# TMC5160_SPI_rev2.net
KiCad netlist of a schematic drawn in EAGLE
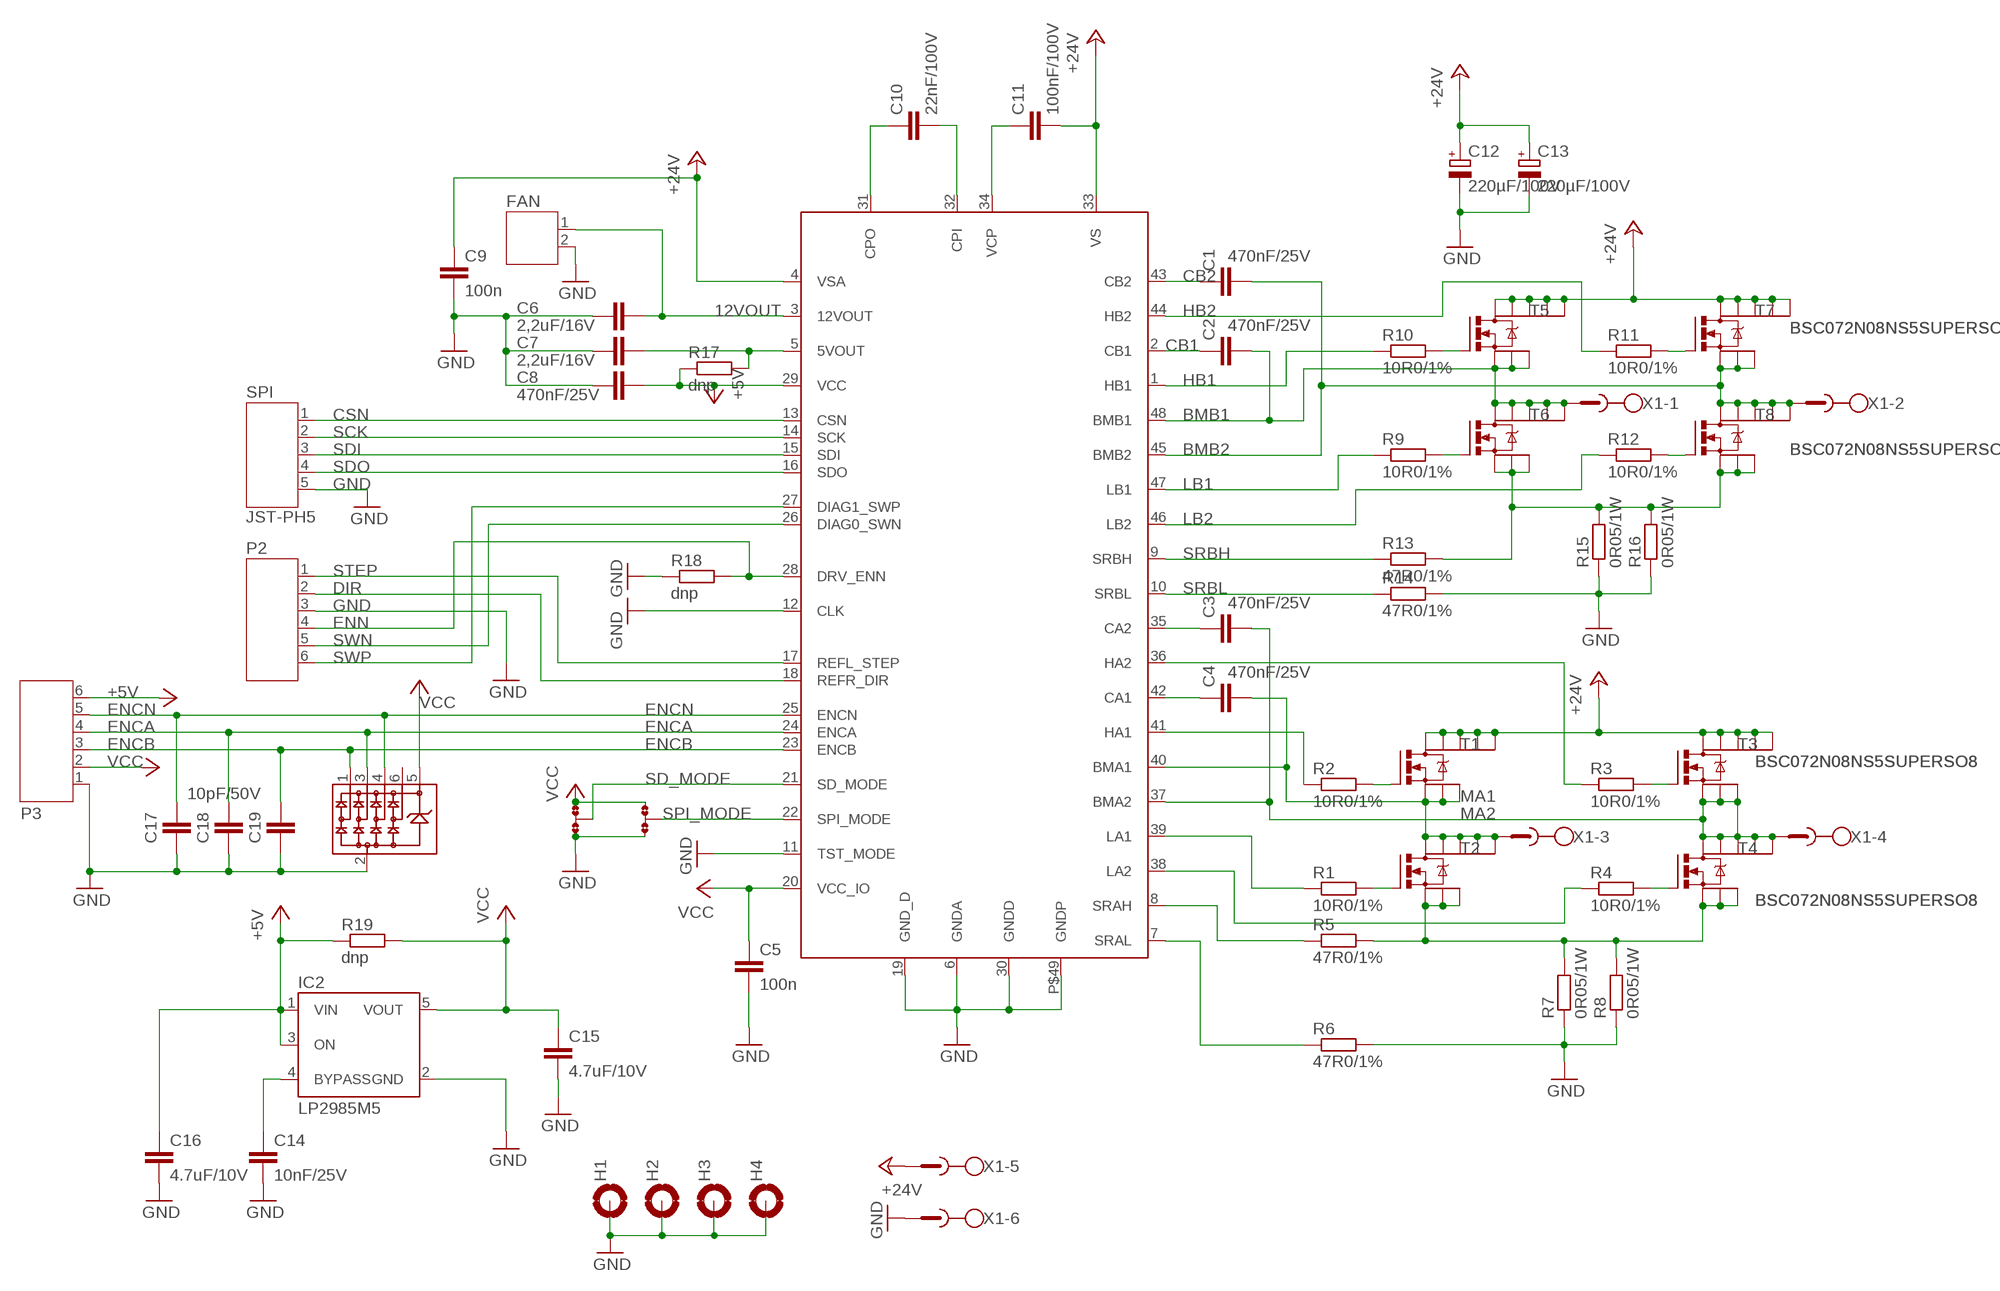
[diagram p0: schematic, sheet 1]

(export (version "E")
  (design (tool "Eeschema 10.0.6"))
  (components
    (comp (ref "C1")
      (value "470nF/25V")
      (footprint "eagle-import:C0805")
      (libsource (lib "eagle-import") (part "C-EUC0805"))
    )
    (comp (ref "C2")
      (value "470nF/25V")
      (footprint "eagle-import:C0805")
      (libsource (lib "eagle-import") (part "C-EUC0805"))
    )
    (comp (ref "C3")
      (value "470nF/25V")
      (footprint "eagle-import:C0805")
      (libsource (lib "eagle-import") (part "C-EUC0805"))
    )
    (comp (ref "C4")
      (value "470nF/25V")
      (footprint "eagle-import:C0805")
      (libsource (lib "eagle-import") (part "C-EUC0805"))
    )
    (comp (ref "C5")
      (value "100n")
      (footprint "eagle-import:C0603")
      (libsource (lib "eagle-import") (part "C-EUC0603"))
    )
    (comp (ref "C6")
      (value "2,2uF/16V")
      (footprint "eagle-import:C0805")
      (libsource (lib "eagle-import") (part "C-EUC0805"))
    )
    (comp (ref "C7")
      (value "2,2uF/16V")
      (footprint "eagle-import:C0805")
      (libsource (lib "eagle-import") (part "C-EUC0805"))
    )
    (comp (ref "C8")
      (value "470nF/25V")
      (footprint "eagle-import:C0805")
      (libsource (lib "eagle-import") (part "C-EUC0805"))
    )
    (comp (ref "C9")
      (value "100n")
      (footprint "eagle-import:C0603")
      (libsource (lib "eagle-import") (part "C-EUC0603"))
    )
    (comp (ref "C10")
      (value "22nF/100V")
      (footprint "eagle-import:C0805")
      (libsource (lib "eagle-import") (part "C-EUC0805"))
    )
    (comp (ref "C11")
      (value "100nF/100V")
      (footprint "eagle-import:C0805")
      (libsource (lib "eagle-import") (part "C-EUC0805"))
    )
    (comp (ref "C12")
      (value "220µF/100V")
      (footprint "eagle-import:153CLV-1014")
      (libsource (lib "eagle-import") (part "CPOL-EU153CLV-1014"))
    )
    (comp (ref "C13")
      (value "220µF/100V")
      (footprint "eagle-import:153CLV-1014")
      (libsource (lib "eagle-import") (part "CPOL-EU153CLV-1014"))
    )
    (comp (ref "C14")
      (value "10nF/25V")
      (footprint "eagle-import:C0603")
      (libsource (lib "eagle-import") (part "C-EUC0603"))
    )
    (comp (ref "C15")
      (value "4.7uF/10V")
      (footprint "eagle-import:C0603")
      (libsource (lib "eagle-import") (part "C-EUC0603"))
    )
    (comp (ref "C16")
      (value "4.7uF/10V")
      (footprint "eagle-import:C0603")
      (libsource (lib "eagle-import") (part "C-EUC0603"))
    )
    (comp (ref "C17")
      (value "10pF/50V")
      (footprint "eagle-import:C0603")
      (libsource (lib "eagle-import") (part "C-EUC0603"))
    )
    (comp (ref "C18")
      (value "10pF/50V")
      (footprint "eagle-import:C0603")
      (libsource (lib "eagle-import") (part "C-EUC0603"))
    )
    (comp (ref "C19")
      (value "10pF/50V")
      (footprint "eagle-import:C0603")
      (libsource (lib "eagle-import") (part "C-EUC0603"))
    )
    (comp (ref "D1")
      (value "SRV05-4SOT23-6-3D")
      (footprint "eagle-import:SOT23-6")
      (libsource (lib "eagle-import") (part "SRV05-4SOT23-6-3D"))
    )
    (comp (ref "FAN")
      (value "JST-PH2")
      (footprint "eagle-import:JST-PH2")
      (libsource (lib "eagle-import") (part "JST-PH2"))
    )
    (comp (ref "H1")
      (value "MOUNT-PAD-ROUND3.2")
      (footprint "eagle-import:3,2-PAD")
      (libsource (lib "eagle-import") (part "MOUNT-PAD-ROUND3.2"))
    )
    (comp (ref "H2")
      (value "MOUNT-PAD-ROUND3.2")
      (footprint "eagle-import:3,2-PAD")
      (libsource (lib "eagle-import") (part "MOUNT-PAD-ROUND3.2"))
    )
    (comp (ref "H3")
      (value "MOUNT-PAD-ROUND3.2")
      (footprint "eagle-import:3,2-PAD")
      (libsource (lib "eagle-import") (part "MOUNT-PAD-ROUND3.2"))
    )
    (comp (ref "H4")
      (value "MOUNT-PAD-ROUND3.2")
      (footprint "eagle-import:3,2-PAD")
      (libsource (lib "eagle-import") (part "MOUNT-PAD-ROUND3.2"))
    )
    (comp (ref "IC2")
      (value "LP2985M5")
      (footprint "eagle-import:SOT23-5")
      (libsource (lib "eagle-import") (part "LP2985M5"))
    )
    (comp (ref "JMP1")
      (value "0R-JUMPA")
      (footprint "eagle-import:A0R-JMP")
      (libsource (lib "eagle-import") (part "0R-JUMPA"))
    )
    (comp (ref "JMP2")
      (value "0R-JUMPA")
      (footprint "eagle-import:A0R-JMP")
      (libsource (lib "eagle-import") (part "0R-JUMPA"))
    )
    (comp (ref "P2")
      (value "JST-PH6")
      (footprint "eagle-import:JST-PH6")
      (libsource (lib "eagle-import") (part "JST-PH6"))
    )
    (comp (ref "P3")
      (value "JST-PH6")
      (footprint "eagle-import:JST-PH6")
      (libsource (lib "eagle-import") (part "JST-PH6"))
    )
    (comp (ref "R1")
      (value "10R0/1%")
      (footprint "eagle-import:R0603")
      (libsource (lib "eagle-import") (part "R-EU_R0603"))
    )
    (comp (ref "R2")
      (value "10R0/1%")
      (footprint "eagle-import:R0603")
      (libsource (lib "eagle-import") (part "R-EU_R0603"))
    )
    (comp (ref "R3")
      (value "10R0/1%")
      (footprint "eagle-import:R0603")
      (libsource (lib "eagle-import") (part "R-EU_R0603"))
    )
    (comp (ref "R4")
      (value "10R0/1%")
      (footprint "eagle-import:R0603")
      (libsource (lib "eagle-import") (part "R-EU_R0603"))
    )
    (comp (ref "R5")
      (value "47R0/1%")
      (footprint "eagle-import:R0603")
      (libsource (lib "eagle-import") (part "R-EU_R0603"))
    )
    (comp (ref "R6")
      (value "47R0/1%")
      (footprint "eagle-import:R0603")
      (libsource (lib "eagle-import") (part "R-EU_R0603"))
    )
    (comp (ref "R7")
      (value "0R05/1W")
      (footprint "eagle-import:R3225")
      (libsource (lib "eagle-import") (part "R-EU_R3225"))
    )
    (comp (ref "R8")
      (value "0R05/1W")
      (footprint "eagle-import:R3225")
      (libsource (lib "eagle-import") (part "R-EU_R3225"))
    )
    (comp (ref "R9")
      (value "10R0/1%")
      (footprint "eagle-import:R0603")
      (libsource (lib "eagle-import") (part "R-EU_R0603"))
    )
    (comp (ref "R10")
      (value "10R0/1%")
      (footprint "eagle-import:R0603")
      (libsource (lib "eagle-import") (part "R-EU_R0603"))
    )
    (comp (ref "R11")
      (value "10R0/1%")
      (footprint "eagle-import:R0603")
      (libsource (lib "eagle-import") (part "R-EU_R0603"))
    )
    (comp (ref "R12")
      (value "10R0/1%")
      (footprint "eagle-import:R0603")
      (libsource (lib "eagle-import") (part "R-EU_R0603"))
    )
    (comp (ref "R13")
      (value "47R0/1%")
      (footprint "eagle-import:R0603")
      (libsource (lib "eagle-import") (part "R-EU_R0603"))
    )
    (comp (ref "R14")
      (value "47R0/1%")
      (footprint "eagle-import:R0603")
      (libsource (lib "eagle-import") (part "R-EU_R0603"))
    )
    (comp (ref "R15")
      (value "0R05/1W")
      (footprint "eagle-import:R3225")
      (libsource (lib "eagle-import") (part "R-EU_R3225"))
    )
    (comp (ref "R16")
      (value "0R05/1W")
      (footprint "eagle-import:R3225")
      (libsource (lib "eagle-import") (part "R-EU_R3225"))
    )
    (comp (ref "R17")
      (value "dnp")
      (footprint "eagle-import:R0603")
      (libsource (lib "eagle-import") (part "R-EU_R0603"))
    )
    (comp (ref "R18")
      (value "dnp")
      (footprint "eagle-import:R0603")
      (libsource (lib "eagle-import") (part "R-EU_R0603"))
    )
    (comp (ref "R19")
      (value "dnp")
      (footprint "eagle-import:R0603")
      (libsource (lib "eagle-import") (part "R-EU_R0603"))
    )
    (comp (ref "SPI")
      (value "JST-PH5")
      (footprint "eagle-import:JST-PH5")
      (libsource (lib "eagle-import") (part "JST-PH5"))
    )
    (comp (ref "T1")
      (value "BSC072N08NS5SUPERSO8")
      (footprint "eagle-import:SOTFL127P615X110-8")
      (libsource (lib "eagle-import") (part "BSC072N08NS5SUPERSO8"))
    )
    (comp (ref "T2")
      (value "BSC072N08NS5SUPERSO8")
      (footprint "eagle-import:SOTFL127P615X110-8")
      (libsource (lib "eagle-import") (part "BSC072N08NS5SUPERSO8"))
    )
    (comp (ref "T3")
      (value "BSC072N08NS5SUPERSO8")
      (footprint "eagle-import:SOTFL127P615X110-8")
      (libsource (lib "eagle-import") (part "BSC072N08NS5SUPERSO8"))
    )
    (comp (ref "T4")
      (value "BSC072N08NS5SUPERSO8")
      (footprint "eagle-import:SOTFL127P615X110-8")
      (libsource (lib "eagle-import") (part "BSC072N08NS5SUPERSO8"))
    )
    (comp (ref "T5")
      (value "BSC072N08NS5SUPERSO8")
      (footprint "eagle-import:SOTFL127P615X110-8")
      (libsource (lib "eagle-import") (part "BSC072N08NS5SUPERSO8"))
    )
    (comp (ref "T6")
      (value "BSC072N08NS5SUPERSO8")
      (footprint "eagle-import:SOTFL127P615X110-8")
      (libsource (lib "eagle-import") (part "BSC072N08NS5SUPERSO8"))
    )
    (comp (ref "T7")
      (value "BSC072N08NS5SUPERSO8")
      (footprint "eagle-import:SOTFL127P615X110-8")
      (libsource (lib "eagle-import") (part "BSC072N08NS5SUPERSO8"))
    )
    (comp (ref "T8")
      (value "BSC072N08NS5SUPERSO8")
      (footprint "eagle-import:SOTFL127P615X110-8")
      (libsource (lib "eagle-import") (part "BSC072N08NS5SUPERSO8"))
    )
    (comp (ref "TMC5160")
      (value "TMC5160-TA")
      (footprint "eagle-import:QFP50P900X900X120-48")
      (libsource (lib "eagle-import") (part "TMC5160-TA"))
    )
    (comp (ref "X1")
      (value "AKL166-06")
      (footprint "eagle-import:AKL166-06")
      (libsource (lib "eagle-import") (part "AKL166-06"))
    )
  )
  (nets
    (net (code "1") (name "+5V") (class "Default")
      (node (ref "C16") (pin "1") (pinfunction "1_1") (pintype "passive"))
      (node (ref "C8") (pin "2") (pinfunction "2_2") (pintype "passive"))
      (node (ref "IC2") (pin "1") (pinfunction "VIN_1") (pintype "power_in"))
      (node (ref "IC2") (pin "3") (pinfunction "ON_3") (pintype "input"))
      (node (ref "P3") (pin "6") (pinfunction "6_6") (pintype "passive"))
      (node (ref "R17") (pin "1") (pinfunction "1_1") (pintype "passive"))
      (node (ref "R19") (pin "1") (pinfunction "1_1") (pintype "passive"))
      (node (ref "TMC5160") (pin "29") (pinfunction "VCC_29") (pintype "bidirectional"))
    )
    (net (code "2") (name "+24V") (class "Default")
      (node (ref "C11") (pin "2") (pinfunction "2_2") (pintype "passive"))
      (node (ref "C12") (pin "+") (pinfunction "+_+") (pintype "passive"))
      (node (ref "C13") (pin "+") (pinfunction "+_+") (pintype "passive"))
      (node (ref "C9") (pin "1") (pinfunction "1_1") (pintype "passive"))
      (node (ref "T1") (pin "D") (pinfunction "D_D") (pintype "passive"))
      (node (ref "T1") (pin "D5") (pinfunction "D1_D5") (pintype "passive"))
      (node (ref "T1") (pin "D6") (pinfunction "D2_D6") (pintype "passive"))
      (node (ref "T1") (pin "D7") (pinfunction "D3_D7") (pintype "passive"))
      (node (ref "T1") (pin "D8") (pinfunction "D4_D8") (pintype "passive"))
      (node (ref "T3") (pin "D") (pinfunction "D_D") (pintype "passive"))
      (node (ref "T3") (pin "D5") (pinfunction "D1_D5") (pintype "passive"))
      (node (ref "T3") (pin "D6") (pinfunction "D2_D6") (pintype "passive"))
      (node (ref "T3") (pin "D7") (pinfunction "D3_D7") (pintype "passive"))
      (node (ref "T3") (pin "D8") (pinfunction "D4_D8") (pintype "passive"))
      (node (ref "T5") (pin "D") (pinfunction "D_D") (pintype "passive"))
      (node (ref "T5") (pin "D5") (pinfunction "D1_D5") (pintype "passive"))
      (node (ref "T5") (pin "D6") (pinfunction "D2_D6") (pintype "passive"))
      (node (ref "T5") (pin "D7") (pinfunction "D3_D7") (pintype "passive"))
      (node (ref "T5") (pin "D8") (pinfunction "D4_D8") (pintype "passive"))
      (node (ref "T7") (pin "D") (pinfunction "D_D") (pintype "passive"))
      (node (ref "T7") (pin "D5") (pinfunction "D1_D5") (pintype "passive"))
      (node (ref "T7") (pin "D6") (pinfunction "D2_D6") (pintype "passive"))
      (node (ref "T7") (pin "D7") (pinfunction "D3_D7") (pintype "passive"))
      (node (ref "T7") (pin "D8") (pinfunction "D4_D8") (pintype "passive"))
      (node (ref "TMC5160") (pin "33") (pinfunction "VS_33") (pintype "bidirectional"))
      (node (ref "TMC5160") (pin "4") (pinfunction "VSA_4") (pintype "bidirectional"))
      (node (ref "X1") (pin "5") (pinfunction "SK_5") (pintype "passive"))
    )
    (net (code "3") (name "/12VOUT") (class "Default")
      (node (ref "C6") (pin "2") (pinfunction "2_2") (pintype "passive"))
      (node (ref "FAN") (pin "1") (pinfunction "1_1") (pintype "passive"))
      (node (ref "TMC5160") (pin "3") (pinfunction "12VOUT_3") (pintype "bidirectional"))
    )
    (net (code "4") (name "/BMB1") (class "Default")
      (node (ref "C2") (pin "2") (pinfunction "2_2") (pintype "passive"))
      (node (ref "T5") (pin "S1") (pinfunction "S1_S1") (pintype "passive"))
      (node (ref "T5") (pin "S2") (pinfunction "S2_S2") (pintype "passive"))
      (node (ref "T5") (pin "S3") (pinfunction "S_S3") (pintype "passive"))
      (node (ref "T6") (pin "D") (pinfunction "D_D") (pintype "passive"))
      (node (ref "T6") (pin "D5") (pinfunction "D1_D5") (pintype "passive"))
      (node (ref "T6") (pin "D6") (pinfunction "D2_D6") (pintype "passive"))
      (node (ref "T6") (pin "D7") (pinfunction "D3_D7") (pintype "passive"))
      (node (ref "T6") (pin "D8") (pinfunction "D4_D8") (pintype "passive"))
      (node (ref "TMC5160") (pin "48") (pinfunction "BMB1_48") (pintype "bidirectional"))
      (node (ref "X1") (pin "1") (pinfunction "SK_1") (pintype "passive"))
    )
    (net (code "5") (name "/BMB2") (class "Default")
      (node (ref "C1") (pin "2") (pinfunction "2_2") (pintype "passive"))
      (node (ref "T7") (pin "S1") (pinfunction "S1_S1") (pintype "passive"))
      (node (ref "T7") (pin "S2") (pinfunction "S2_S2") (pintype "passive"))
      (node (ref "T7") (pin "S3") (pinfunction "S_S3") (pintype "passive"))
      (node (ref "T8") (pin "D") (pinfunction "D_D") (pintype "passive"))
      (node (ref "T8") (pin "D5") (pinfunction "D1_D5") (pintype "passive"))
      (node (ref "T8") (pin "D6") (pinfunction "D2_D6") (pintype "passive"))
      (node (ref "T8") (pin "D7") (pinfunction "D3_D7") (pintype "passive"))
      (node (ref "T8") (pin "D8") (pinfunction "D4_D8") (pintype "passive"))
      (node (ref "TMC5160") (pin "45") (pinfunction "BMB2_45") (pintype "bidirectional"))
      (node (ref "X1") (pin "2") (pinfunction "SK_2") (pintype "passive"))
    )
    (net (code "6") (name "/CB1") (class "Default")
      (node (ref "C2") (pin "1") (pinfunction "1_1") (pintype "passive"))
      (node (ref "TMC5160") (pin "2") (pinfunction "CB1_2") (pintype "bidirectional"))
    )
    (net (code "7") (name "/CB2") (class "Default")
      (node (ref "C1") (pin "1") (pinfunction "1_1") (pintype "passive"))
      (node (ref "TMC5160") (pin "43") (pinfunction "CB2_43") (pintype "bidirectional"))
    )
    (net (code "8") (name "/CSN") (class "Default")
      (node (ref "SPI") (pin "1") (pinfunction "1_1") (pintype "passive"))
      (node (ref "TMC5160") (pin "13") (pinfunction "CSN_13") (pintype "bidirectional"))
    )
    (net (code "9") (name "/DIR") (class "Default")
      (node (ref "P2") (pin "2") (pinfunction "2_2") (pintype "passive"))
      (node (ref "TMC5160") (pin "18") (pinfunction "REFR_DIR_18") (pintype "bidirectional"))
    )
    (net (code "10") (name "/ENCA") (class "Default")
      (node (ref "C18") (pin "1") (pinfunction "1_1") (pintype "passive"))
      (node (ref "D1") (pin "3") (pinfunction "3_3") (pintype "bidirectional"))
      (node (ref "P3") (pin "4") (pinfunction "4_4") (pintype "passive"))
      (node (ref "TMC5160") (pin "24") (pinfunction "ENCA_24") (pintype "bidirectional"))
    )
    (net (code "11") (name "/ENCB") (class "Default")
      (node (ref "C19") (pin "1") (pinfunction "1_1") (pintype "passive"))
      (node (ref "D1") (pin "1") (pinfunction "1_1") (pintype "bidirectional"))
      (node (ref "P3") (pin "3") (pinfunction "3_3") (pintype "passive"))
      (node (ref "TMC5160") (pin "23") (pinfunction "ENCB_23") (pintype "bidirectional"))
    )
    (net (code "12") (name "/ENCN") (class "Default")
      (node (ref "C17") (pin "1") (pinfunction "1_1") (pintype "passive"))
      (node (ref "D1") (pin "4") (pinfunction "4_4") (pintype "bidirectional"))
      (node (ref "P3") (pin "5") (pinfunction "5_5") (pintype "passive"))
      (node (ref "TMC5160") (pin "25") (pinfunction "ENCN_25") (pintype "bidirectional"))
    )
    (net (code "13") (name "/ENN") (class "Default")
      (node (ref "P2") (pin "4") (pinfunction "4_4") (pintype "passive"))
      (node (ref "R18") (pin "2") (pinfunction "2_2") (pintype "passive"))
      (node (ref "TMC5160") (pin "28") (pinfunction "DRV_ENN_28") (pintype "bidirectional"))
    )
    (net (code "14") (name "/HB1") (class "Default")
      (node (ref "R10") (pin "1") (pinfunction "1_1") (pintype "passive"))
      (node (ref "TMC5160") (pin "1") (pinfunction "HB1_1") (pintype "bidirectional"))
    )
    (net (code "15") (name "/HB2") (class "Default")
      (node (ref "R11") (pin "1") (pinfunction "1_1") (pintype "passive"))
      (node (ref "TMC5160") (pin "44") (pinfunction "HB2_44") (pintype "bidirectional"))
    )
    (net (code "16") (name "/LB1") (class "Default")
      (node (ref "R9") (pin "1") (pinfunction "1_1") (pintype "passive"))
      (node (ref "TMC5160") (pin "47") (pinfunction "LB1_47") (pintype "bidirectional"))
    )
    (net (code "17") (name "/LB2") (class "Default")
      (node (ref "R12") (pin "1") (pinfunction "1_1") (pintype "passive"))
      (node (ref "TMC5160") (pin "46") (pinfunction "LB2_46") (pintype "bidirectional"))
    )
    (net (code "18") (name "/MA1") (class "Default")
      (node (ref "C4") (pin "2") (pinfunction "2_2") (pintype "passive"))
      (node (ref "T1") (pin "S1") (pinfunction "S1_S1") (pintype "passive"))
      (node (ref "T1") (pin "S2") (pinfunction "S2_S2") (pintype "passive"))
      (node (ref "T1") (pin "S3") (pinfunction "S_S3") (pintype "passive"))
      (node (ref "T2") (pin "D") (pinfunction "D_D") (pintype "passive"))
      (node (ref "T2") (pin "D5") (pinfunction "D1_D5") (pintype "passive"))
      (node (ref "T2") (pin "D6") (pinfunction "D2_D6") (pintype "passive"))
      (node (ref "T2") (pin "D7") (pinfunction "D3_D7") (pintype "passive"))
      (node (ref "T2") (pin "D8") (pinfunction "D4_D8") (pintype "passive"))
      (node (ref "TMC5160") (pin "40") (pinfunction "BMA1_40") (pintype "bidirectional"))
      (node (ref "X1") (pin "3") (pinfunction "SK_3") (pintype "passive"))
    )
    (net (code "19") (name "/MA2") (class "Default")
      (node (ref "C3") (pin "2") (pinfunction "2_2") (pintype "passive"))
      (node (ref "T3") (pin "S1") (pinfunction "S1_S1") (pintype "passive"))
      (node (ref "T3") (pin "S2") (pinfunction "S2_S2") (pintype "passive"))
      (node (ref "T3") (pin "S3") (pinfunction "S_S3") (pintype "passive"))
      (node (ref "T4") (pin "D") (pinfunction "D_D") (pintype "passive"))
      (node (ref "T4") (pin "D5") (pinfunction "D1_D5") (pintype "passive"))
      (node (ref "T4") (pin "D6") (pinfunction "D2_D6") (pintype "passive"))
      (node (ref "T4") (pin "D7") (pinfunction "D3_D7") (pintype "passive"))
      (node (ref "T4") (pin "D8") (pinfunction "D4_D8") (pintype "passive"))
      (node (ref "TMC5160") (pin "37") (pinfunction "BMA2_37") (pintype "bidirectional"))
      (node (ref "X1") (pin "4") (pinfunction "SK_4") (pintype "passive"))
    )
    (net (code "20") (name "/SCK") (class "Default")
      (node (ref "SPI") (pin "2") (pinfunction "2_2") (pintype "passive"))
      (node (ref "TMC5160") (pin "14") (pinfunction "SCK_14") (pintype "bidirectional"))
    )
    (net (code "21") (name "/SDI") (class "Default")
      (node (ref "SPI") (pin "3") (pinfunction "3_3") (pintype "passive"))
      (node (ref "TMC5160") (pin "15") (pinfunction "SDI_15") (pintype "bidirectional"))
    )
    (net (code "22") (name "/SDO") (class "Default")
      (node (ref "SPI") (pin "4") (pinfunction "4_4") (pintype "passive"))
      (node (ref "TMC5160") (pin "16") (pinfunction "SDO_16") (pintype "bidirectional"))
    )
    (net (code "23") (name "/SD_MODE") (class "Default")
      (node (ref "JMP1") (pin "2") (pinfunction "2_2") (pintype "passive"))
      (node (ref "TMC5160") (pin "21") (pinfunction "SD_MODE_21") (pintype "bidirectional"))
    )
    (net (code "24") (name "/SPI_MODE") (class "Default")
      (node (ref "JMP2") (pin "2") (pinfunction "2_2") (pintype "passive"))
      (node (ref "TMC5160") (pin "22") (pinfunction "SPI_MODE_22") (pintype "bidirectional"))
    )
    (net (code "25") (name "/SRBH") (class "Default")
      (node (ref "R13") (pin "1") (pinfunction "1_1") (pintype "passive"))
      (node (ref "TMC5160") (pin "9") (pinfunction "SRBH_9") (pintype "bidirectional"))
    )
    (net (code "26") (name "/SRBL") (class "Default")
      (node (ref "R14") (pin "1") (pinfunction "1_1") (pintype "passive"))
      (node (ref "TMC5160") (pin "10") (pinfunction "SRBL_10") (pintype "bidirectional"))
    )
    (net (code "27") (name "/STEP") (class "Default")
      (node (ref "P2") (pin "1") (pinfunction "1_1") (pintype "passive"))
      (node (ref "TMC5160") (pin "17") (pinfunction "REFL_STEP_17") (pintype "bidirectional"))
    )
    (net (code "28") (name "/SWN") (class "Default")
      (node (ref "P2") (pin "5") (pinfunction "5_5") (pintype "passive"))
      (node (ref "TMC5160") (pin "26") (pinfunction "DIAG0_SWN_26") (pintype "bidirectional"))
    )
    (net (code "29") (name "/SWP") (class "Default")
      (node (ref "P2") (pin "6") (pinfunction "6_6") (pintype "passive"))
      (node (ref "TMC5160") (pin "27") (pinfunction "DIAG1_SWP_27") (pintype "bidirectional"))
    )
    (net (code "30") (name "GND") (class "Default")
      (node (ref "C12") (pin "-") (pinfunction "-_-") (pintype "passive"))
      (node (ref "C13") (pin "-") (pinfunction "-_-") (pintype "passive"))
      (node (ref "C14") (pin "2") (pinfunction "2_2") (pintype "passive"))
      (node (ref "C15") (pin "2") (pinfunction "2_2") (pintype "passive"))
      (node (ref "C16") (pin "2") (pinfunction "2_2") (pintype "passive"))
      (node (ref "C17") (pin "2") (pinfunction "2_2") (pintype "passive"))
      (node (ref "C18") (pin "2") (pinfunction "2_2") (pintype "passive"))
      (node (ref "C19") (pin "2") (pinfunction "2_2") (pintype "passive"))
      (node (ref "C5") (pin "2") (pinfunction "2_2") (pintype "passive"))
      (node (ref "C6") (pin "1") (pinfunction "1_1") (pintype "passive"))
      (node (ref "C7") (pin "2") (pinfunction "2_2") (pintype "passive"))
      (node (ref "C8") (pin "1") (pinfunction "1_1") (pintype "passive"))
      (node (ref "C9") (pin "2") (pinfunction "2_2") (pintype "passive"))
      (node (ref "D1") (pin "2") (pinfunction "2_2") (pintype "bidirectional"))
      (node (ref "FAN") (pin "2") (pinfunction "2_2") (pintype "passive"))
      (node (ref "H1") (pin "B3,2") (pinfunction "MOUNT_B3,2") (pintype "passive"))
      (node (ref "H2") (pin "B3,2") (pinfunction "MOUNT_B3,2") (pintype "passive"))
      (node (ref "H3") (pin "B3,2") (pinfunction "MOUNT_B3,2") (pintype "passive"))
      (node (ref "H4") (pin "B3,2") (pinfunction "MOUNT_B3,2") (pintype "passive"))
      (node (ref "IC2") (pin "2") (pinfunction "GND_2") (pintype "power_in"))
      (node (ref "JMP1") (pin "3") (pinfunction "3_3") (pintype "passive"))
      (node (ref "JMP2") (pin "3") (pinfunction "3_3") (pintype "passive"))
      (node (ref "P2") (pin "3") (pinfunction "3_3") (pintype "passive"))
      (node (ref "P3") (pin "1") (pinfunction "1_1") (pintype "passive"))
      (node (ref "R14") (pin "2") (pinfunction "2_2") (pintype "passive"))
      (node (ref "R15") (pin "1") (pinfunction "1_1") (pintype "passive"))
      (node (ref "R16") (pin "1") (pinfunction "1_1") (pintype "passive"))
      (node (ref "R18") (pin "1") (pinfunction "1_1") (pintype "passive"))
      (node (ref "R6") (pin "2") (pinfunction "2_2") (pintype "passive"))
      (node (ref "R7") (pin "1") (pinfunction "1_1") (pintype "passive"))
      (node (ref "R8") (pin "1") (pinfunction "1_1") (pintype "passive"))
      (node (ref "SPI") (pin "5") (pinfunction "5_5") (pintype "passive"))
      (node (ref "TMC5160") (pin "11") (pinfunction "TST_MODE_11") (pintype "bidirectional"))
      (node (ref "TMC5160") (pin "12") (pinfunction "CLK_12") (pintype "bidirectional"))
      (node (ref "TMC5160") (pin "19") (pinfunction "GND_D_19") (pintype "bidirectional"))
      (node (ref "TMC5160") (pin "30") (pinfunction "GNDD_30") (pintype "bidirectional"))
      (node (ref "TMC5160") (pin "6") (pinfunction "GNDA_6") (pintype "bidirectional"))
      (node (ref "TMC5160") (pin "P$49") (pinfunction "GNDP_P$49") (pintype "bidirectional"))
      (node (ref "X1") (pin "6") (pinfunction "SK_6") (pintype "passive"))
    )
    (net (code "31") (name "Net-(IC2-BYPASS)") (class "Default")
      (node (ref "C14") (pin "1") (pinfunction "1_1") (pintype "passive"))
      (node (ref "IC2") (pin "4") (pinfunction "BYPASS_4") (pintype "passive"))
    )
    (net (code "32") (name "Net-(R1-Pad2)") (class "Default")
      (node (ref "R1") (pin "2") (pinfunction "2_2") (pintype "passive"))
      (node (ref "T2") (pin "G") (pinfunction "G_G") (pintype "passive"))
    )
    (net (code "33") (name "Net-(R2-Pad2)") (class "Default")
      (node (ref "R2") (pin "2") (pinfunction "2_2") (pintype "passive"))
      (node (ref "T1") (pin "G") (pinfunction "G_G") (pintype "passive"))
    )
    (net (code "34") (name "Net-(R3-Pad2)") (class "Default")
      (node (ref "R3") (pin "2") (pinfunction "2_2") (pintype "passive"))
      (node (ref "T3") (pin "G") (pinfunction "G_G") (pintype "passive"))
    )
    (net (code "35") (name "Net-(R4-Pad2)") (class "Default")
      (node (ref "R4") (pin "2") (pinfunction "2_2") (pintype "passive"))
      (node (ref "T4") (pin "G") (pinfunction "G_G") (pintype "passive"))
    )
    (net (code "36") (name "Net-(R9-Pad2)") (class "Default")
      (node (ref "R9") (pin "2") (pinfunction "2_2") (pintype "passive"))
      (node (ref "T6") (pin "G") (pinfunction "G_G") (pintype "passive"))
    )
    (net (code "37") (name "Net-(R10-Pad2)") (class "Default")
      (node (ref "R10") (pin "2") (pinfunction "2_2") (pintype "passive"))
      (node (ref "T5") (pin "G") (pinfunction "G_G") (pintype "passive"))
    )
    (net (code "38") (name "Net-(R11-Pad2)") (class "Default")
      (node (ref "R11") (pin "2") (pinfunction "2_2") (pintype "passive"))
      (node (ref "T7") (pin "G") (pinfunction "G_G") (pintype "passive"))
    )
    (net (code "39") (name "Net-(R12-Pad2)") (class "Default")
      (node (ref "R12") (pin "2") (pinfunction "2_2") (pintype "passive"))
      (node (ref "T8") (pin "G") (pinfunction "G_G") (pintype "passive"))
    )
    (net (code "40") (name "Net-(T2-S)") (class "Default")
      (node (ref "R5") (pin "2") (pinfunction "2_2") (pintype "passive"))
      (node (ref "R7") (pin "2") (pinfunction "2_2") (pintype "passive"))
      (node (ref "R8") (pin "2") (pinfunction "2_2") (pintype "passive"))
      (node (ref "T2") (pin "S1") (pinfunction "S1_S1") (pintype "passive"))
      (node (ref "T2") (pin "S2") (pinfunction "S2_S2") (pintype "passive"))
      (node (ref "T2") (pin "S3") (pinfunction "S_S3") (pintype "passive"))
      (node (ref "T4") (pin "S1") (pinfunction "S1_S1") (pintype "passive"))
      (node (ref "T4") (pin "S2") (pinfunction "S2_S2") (pintype "passive"))
      (node (ref "T4") (pin "S3") (pinfunction "S_S3") (pintype "passive"))
    )
    (net (code "41") (name "Net-(T6-S)") (class "Default")
      (node (ref "R13") (pin "2") (pinfunction "2_2") (pintype "passive"))
      (node (ref "R15") (pin "2") (pinfunction "2_2") (pintype "passive"))
      (node (ref "R16") (pin "2") (pinfunction "2_2") (pintype "passive"))
      (node (ref "T6") (pin "S1") (pinfunction "S1_S1") (pintype "passive"))
      (node (ref "T6") (pin "S2") (pinfunction "S2_S2") (pintype "passive"))
      (node (ref "T6") (pin "S3") (pinfunction "S_S3") (pintype "passive"))
      (node (ref "T8") (pin "S1") (pinfunction "S1_S1") (pintype "passive"))
      (node (ref "T8") (pin "S2") (pinfunction "S2_S2") (pintype "passive"))
      (node (ref "T8") (pin "S3") (pinfunction "S_S3") (pintype "passive"))
    )
    (net (code "42") (name "Net-(TMC5160-5VOUT)") (class "Default")
      (node (ref "C7") (pin "1") (pinfunction "1_1") (pintype "passive"))
      (node (ref "R17") (pin "2") (pinfunction "2_2") (pintype "passive"))
      (node (ref "TMC5160") (pin "5") (pinfunction "5VOUT_5") (pintype "bidirectional"))
    )
    (net (code "43") (name "Net-(TMC5160-CA1)") (class "Default")
      (node (ref "C4") (pin "1") (pinfunction "1_1") (pintype "passive"))
      (node (ref "TMC5160") (pin "42") (pinfunction "CA1_42") (pintype "bidirectional"))
    )
    (net (code "44") (name "Net-(TMC5160-CA2)") (class "Default")
      (node (ref "C3") (pin "1") (pinfunction "1_1") (pintype "passive"))
      (node (ref "TMC5160") (pin "35") (pinfunction "CA2_35") (pintype "bidirectional"))
    )
    (net (code "45") (name "Net-(TMC5160-CPI)") (class "Default")
      (node (ref "C10") (pin "2") (pinfunction "2_2") (pintype "passive"))
      (node (ref "TMC5160") (pin "32") (pinfunction "CPI_32") (pintype "bidirectional"))
    )
    (net (code "46") (name "Net-(TMC5160-CPO)") (class "Default")
      (node (ref "C10") (pin "1") (pinfunction "1_1") (pintype "passive"))
      (node (ref "TMC5160") (pin "31") (pinfunction "CPO_31") (pintype "bidirectional"))
    )
    (net (code "47") (name "Net-(TMC5160-HA1)") (class "Default")
      (node (ref "R2") (pin "1") (pinfunction "1_1") (pintype "passive"))
      (node (ref "TMC5160") (pin "41") (pinfunction "HA1_41") (pintype "bidirectional"))
    )
    (net (code "48") (name "Net-(TMC5160-HA2)") (class "Default")
      (node (ref "R3") (pin "1") (pinfunction "1_1") (pintype "passive"))
      (node (ref "TMC5160") (pin "36") (pinfunction "HA2_36") (pintype "bidirectional"))
    )
    (net (code "49") (name "Net-(TMC5160-LA1)") (class "Default")
      (node (ref "R1") (pin "1") (pinfunction "1_1") (pintype "passive"))
      (node (ref "TMC5160") (pin "39") (pinfunction "LA1_39") (pintype "bidirectional"))
    )
    (net (code "50") (name "Net-(TMC5160-LA2)") (class "Default")
      (node (ref "R4") (pin "1") (pinfunction "1_1") (pintype "passive"))
      (node (ref "TMC5160") (pin "38") (pinfunction "LA2_38") (pintype "bidirectional"))
    )
    (net (code "51") (name "Net-(TMC5160-SRAH)") (class "Default")
      (node (ref "R5") (pin "1") (pinfunction "1_1") (pintype "passive"))
      (node (ref "TMC5160") (pin "8") (pinfunction "SRAH_8") (pintype "bidirectional"))
    )
    (net (code "52") (name "Net-(TMC5160-SRAL)") (class "Default")
      (node (ref "R6") (pin "1") (pinfunction "1_1") (pintype "passive"))
      (node (ref "TMC5160") (pin "7") (pinfunction "SRAL_7") (pintype "bidirectional"))
    )
    (net (code "53") (name "Net-(TMC5160-VCP)") (class "Default")
      (node (ref "C11") (pin "1") (pinfunction "1_1") (pintype "passive"))
      (node (ref "TMC5160") (pin "34") (pinfunction "VCP_34") (pintype "bidirectional"))
    )
    (net (code "54") (name "VCC") (class "Default")
      (node (ref "C15") (pin "1") (pinfunction "1_1") (pintype "passive"))
      (node (ref "C5") (pin "1") (pinfunction "1_1") (pintype "passive"))
      (node (ref "D1") (pin "5") (pinfunction "5_5") (pintype "bidirectional"))
      (node (ref "IC2") (pin "5") (pinfunction "VOUT_5") (pintype "output"))
      (node (ref "JMP1") (pin "1") (pinfunction "1_1") (pintype "passive"))
      (node (ref "JMP2") (pin "1") (pinfunction "1_1") (pintype "passive"))
      (node (ref "P3") (pin "2") (pinfunction "2_2") (pintype "passive"))
      (node (ref "R19") (pin "2") (pinfunction "2_2") (pintype "passive"))
      (node (ref "TMC5160") (pin "20") (pinfunction "VCC_IO_20") (pintype "bidirectional"))
    )
    (net (code "55") (name "unconnected-(D1-Pad6)") (class "Default")
      (node (ref "D1") (pin "6") (pinfunction "6_6") (pintype "bidirectional"))
    )
  )
)
